# rfid_part.net
KiCad netlist of a schematic drawn in EAGLE
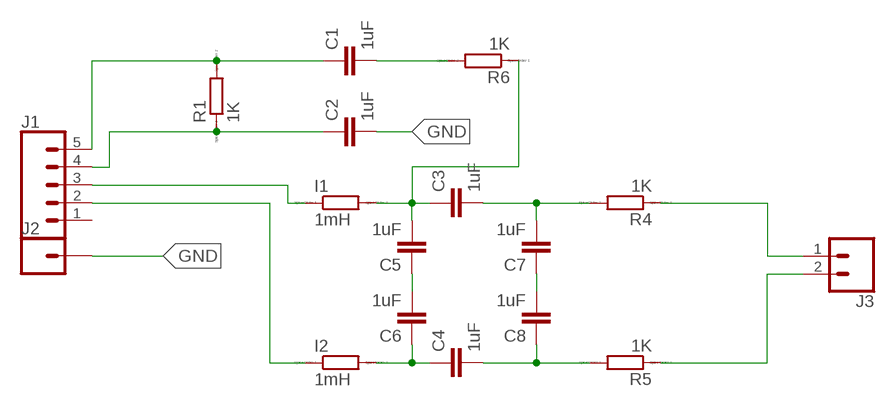
[diagram p0: schematic, sheet 1]

(export (version "E")
  (design (tool "Eeschema 10.0.6"))
  (components
    (comp (ref "C1")
      (value "1uF")
      (footprint "eagle-import:C0603")
      (libsource (lib "eagle-import") (part "C-EUC0603"))
    )
    (comp (ref "C2")
      (value "1uF")
      (footprint "eagle-import:C0603")
      (libsource (lib "eagle-import") (part "C-EUC0603"))
    )
    (comp (ref "C3")
      (value "1uF")
      (footprint "eagle-import:C0603")
      (libsource (lib "eagle-import") (part "C-EUC0603"))
    )
    (comp (ref "C4")
      (value "1uF")
      (footprint "eagle-import:C0603")
      (libsource (lib "eagle-import") (part "C-EUC0603"))
    )
    (comp (ref "C5")
      (value "1uF")
      (footprint "eagle-import:C0603")
      (libsource (lib "eagle-import") (part "C-EUC0603"))
    )
    (comp (ref "C6")
      (value "1uF")
      (footprint "eagle-import:C0603")
      (libsource (lib "eagle-import") (part "C-EUC0603"))
    )
    (comp (ref "C7")
      (value "1uF")
      (footprint "eagle-import:C0603")
      (libsource (lib "eagle-import") (part "C-EUC0603"))
    )
    (comp (ref "C8")
      (value "1uF")
      (footprint "eagle-import:C0603")
      (libsource (lib "eagle-import") (part "C-EUC0603"))
    )
    (comp (ref "I1")
      (value "1mH")
      (footprint "eagle-import:R0603")
      (libsource (lib "eagle-import") (part "RR0603"))
    )
    (comp (ref "I2")
      (value "1mH")
      (footprint "eagle-import:R0603")
      (libsource (lib "eagle-import") (part "RR0603"))
    )
    (comp (ref "J1")
      (value "CONN_05")
      (footprint "eagle-import:1X05")
      (libsource (lib "eagle-import") (part "CONN_05"))
    )
    (comp (ref "J2")
      (value "CONN_01")
      (footprint "eagle-import:1X01")
      (libsource (lib "eagle-import") (part "CONN_01"))
    )
    (comp (ref "J3")
      (value "CONN_02")
      (footprint "eagle-import:1X02")
      (libsource (lib "eagle-import") (part "CONN_02"))
    )
    (comp (ref "R1")
      (value "1K")
      (footprint "eagle-import:R0603")
      (libsource (lib "eagle-import") (part "RR0603"))
    )
    (comp (ref "R4")
      (value "1K")
      (footprint "eagle-import:R0603")
      (libsource (lib "eagle-import") (part "RR0603"))
    )
    (comp (ref "R5")
      (value "1K")
      (footprint "eagle-import:R0603")
      (libsource (lib "eagle-import") (part "RR0603"))
    )
    (comp (ref "R6")
      (value "1K")
      (footprint "eagle-import:R0603")
      (libsource (lib "eagle-import") (part "RR0603"))
    )
  )
  (nets
    (net (code "1") (name "GND") (class "Default")
      (node (ref "C2") (pin "2") (pinfunction "2_2") (pintype "passive"))
      (node (ref "J2") (pin "1") (pinfunction "1_1") (pintype "passive"))
    )
    (net (code "2") (name "Net-(C1-Pad1)") (class "Default")
      (node (ref "C1") (pin "1") (pinfunction "1_1") (pintype "passive"))
      (node (ref "J1") (pin "5") (pinfunction "5_5") (pintype "passive"))
      (node (ref "R1") (pin "2") (pinfunction "2_2") (pintype "passive"))
    )
    (net (code "3") (name "Net-(C1-Pad2)") (class "Default")
      (node (ref "C1") (pin "2") (pinfunction "2_2") (pintype "passive"))
      (node (ref "R6") (pin "2") (pinfunction "2_2") (pintype "passive"))
    )
    (net (code "4") (name "Net-(C2-Pad1)") (class "Default")
      (node (ref "C2") (pin "1") (pinfunction "1_1") (pintype "passive"))
      (node (ref "J1") (pin "4") (pinfunction "4_4") (pintype "passive"))
      (node (ref "R1") (pin "1") (pinfunction "1_1") (pintype "passive"))
    )
    (net (code "5") (name "Net-(C3-Pad1)") (class "Default")
      (node (ref "C3") (pin "1") (pinfunction "1_1") (pintype "passive"))
      (node (ref "C5") (pin "2") (pinfunction "2_2") (pintype "passive"))
      (node (ref "I1") (pin "2") (pinfunction "2_2") (pintype "passive"))
      (node (ref "R6") (pin "1") (pinfunction "1_1") (pintype "passive"))
    )
    (net (code "6") (name "Net-(C3-Pad2)") (class "Default")
      (node (ref "C3") (pin "2") (pinfunction "2_2") (pintype "passive"))
      (node (ref "C7") (pin "2") (pinfunction "2_2") (pintype "passive"))
      (node (ref "R4") (pin "2") (pinfunction "2_2") (pintype "passive"))
    )
    (net (code "7") (name "Net-(C4-Pad1)") (class "Default")
      (node (ref "C4") (pin "1") (pinfunction "1_1") (pintype "passive"))
      (node (ref "C6") (pin "1") (pinfunction "1_1") (pintype "passive"))
      (node (ref "I2") (pin "2") (pinfunction "2_2") (pintype "passive"))
    )
    (net (code "8") (name "Net-(C4-Pad2)") (class "Default")
      (node (ref "C4") (pin "2") (pinfunction "2_2") (pintype "passive"))
      (node (ref "C8") (pin "1") (pinfunction "1_1") (pintype "passive"))
      (node (ref "R5") (pin "2") (pinfunction "2_2") (pintype "passive"))
    )
    (net (code "9") (name "Net-(C5-Pad1)") (class "Default")
      (node (ref "C5") (pin "1") (pinfunction "1_1") (pintype "passive"))
      (node (ref "C6") (pin "2") (pinfunction "2_2") (pintype "passive"))
    )
    (net (code "10") (name "Net-(C7-Pad1)") (class "Default")
      (node (ref "C7") (pin "1") (pinfunction "1_1") (pintype "passive"))
      (node (ref "C8") (pin "2") (pinfunction "2_2") (pintype "passive"))
    )
    (net (code "11") (name "Net-(I1-Pad1)") (class "Default")
      (node (ref "I1") (pin "1") (pinfunction "1_1") (pintype "passive"))
      (node (ref "J1") (pin "3") (pinfunction "3_3") (pintype "passive"))
    )
    (net (code "12") (name "Net-(I2-Pad1)") (class "Default")
      (node (ref "I2") (pin "1") (pinfunction "1_1") (pintype "passive"))
      (node (ref "J1") (pin "2") (pinfunction "2_2") (pintype "passive"))
    )
    (net (code "13") (name "Net-(J3-Pad1)") (class "Default")
      (node (ref "J3") (pin "1") (pinfunction "1_1") (pintype "passive"))
      (node (ref "R4") (pin "1") (pinfunction "1_1") (pintype "passive"))
    )
    (net (code "14") (name "Net-(J3-Pad2)") (class "Default")
      (node (ref "J3") (pin "2") (pinfunction "2_2") (pintype "passive"))
      (node (ref "R5") (pin "1") (pinfunction "1_1") (pintype "passive"))
    )
    (net (code "15") (name "unconnected-(J1-Pad1)") (class "Default")
      (node (ref "J1") (pin "1") (pinfunction "1_1") (pintype "passive"))
    )
  )
)
